# ZYNQ_SOC_JTAG.net
KiCad netlist of a schematic drawn in Altium Designer
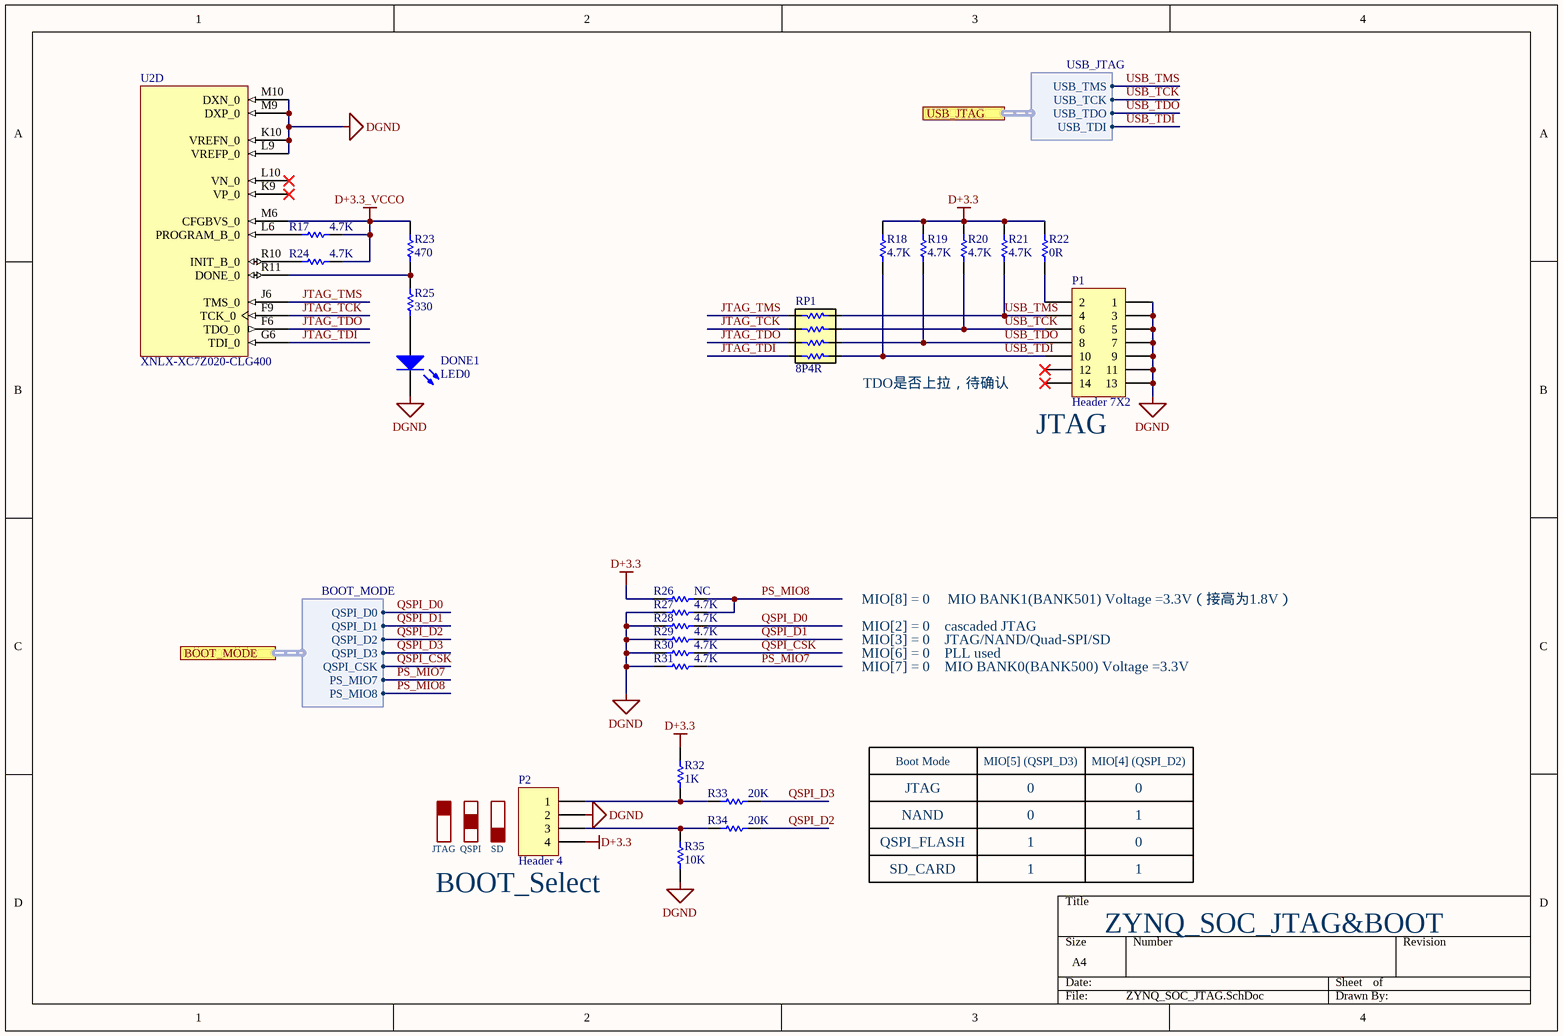
[diagram p0: ZYNQ_SOC_JTAG.SchDoc]

(export (version "E")
  (design (tool "Eeschema 10.0.6"))
  (components
    (comp (ref "DONE1")
      (value "LED0")
      (footprint "LED 0603G")
      (description "Typical INFRARED GaAs LED")
      (fields (field (name "PUBLISHER") "Altium Limited"))
      (libsource (lib "Miscellaneous Devices") (part "LED0"))
    )
    (comp (ref "P1")
      (value "Header 7X2")
      (footprint "IDC2.54-LI-2x7P")
      (description "Header, 7-Pin, Dual row")
      (fields (field (name "PUBLISHER") "Altium Limited"))
      (libsource (lib "Miscellaneous Connectors") (part "Header 7X2"))
    )
    (comp (ref "P2")
      (value "Header 4")
      (footprint "HDR1X4")
      (description "Header, 4-Pin")
      (fields (field (name "PUBLISHER") "Altium Limited"))
      (libsource (lib "Miscellaneous Connectors") (part "Header 4"))
    )
    (comp (ref "R17")
      (value "4.7K")
      (footprint "R 0402_L")
      (description "Resistor")
      (fields (field (name "PUBLISHER") "Altium Limited"))
      (libsource (lib "Miscellaneous Devices") (part "Res1"))
    )
    (comp (ref "R18")
      (value "4.7K")
      (footprint "R 0603_L")
      (description "Resistor")
      (fields (field (name "PUBLISHER") "Altium Limited"))
      (libsource (lib "Miscellaneous Devices") (part "Res1"))
    )
    (comp (ref "R19")
      (value "4.7K")
      (footprint "R 0603_L")
      (description "Resistor")
      (fields (field (name "PUBLISHER") "Altium Limited"))
      (libsource (lib "Miscellaneous Devices") (part "Res1"))
    )
    (comp (ref "R20")
      (value "4.7K")
      (footprint "R 0603_L")
      (description "Resistor")
      (fields (field (name "PUBLISHER") "Altium Limited"))
      (libsource (lib "Miscellaneous Devices") (part "Res1"))
    )
    (comp (ref "R21")
      (value "4.7K")
      (footprint "R 0603_L")
      (description "Resistor")
      (fields (field (name "PUBLISHER") "Altium Limited"))
      (libsource (lib "Miscellaneous Devices") (part "Res1"))
    )
    (comp (ref "R22")
      (value "0R")
      (footprint "R 0603_L")
      (description "Resistor")
      (fields (field (name "PUBLISHER") "Altium Limited"))
      (libsource (lib "Miscellaneous Devices") (part "Res1"))
    )
    (comp (ref "R23")
      (value "470")
      (footprint "R 0603_L")
      (description "Resistor")
      (fields (field (name "PUBLISHER") "Altium Limited"))
      (libsource (lib "Miscellaneous Devices") (part "Res1"))
    )
    (comp (ref "R24")
      (value "4.7K")
      (footprint "R 0402_L")
      (description "Resistor")
      (fields (field (name "PUBLISHER") "Altium Limited"))
      (libsource (lib "Miscellaneous Devices") (part "Res1"))
    )
    (comp (ref "R25")
      (value "330")
      (footprint "R 0603_L")
      (description "Resistor")
      (fields (field (name "PUBLISHER") "Altium Limited"))
      (libsource (lib "Miscellaneous Devices") (part "Res1"))
    )
    (comp (ref "R26")
      (value "NC")
      (footprint "R 0402_L")
      (description "Resistor")
      (fields (field (name "PUBLISHER") "Altium Limited"))
      (libsource (lib "Miscellaneous Devices") (part "Res1"))
    )
    (comp (ref "R27")
      (value "4.7K")
      (footprint "R 0402_L")
      (description "Resistor")
      (fields (field (name "PUBLISHER") "Altium Limited"))
      (libsource (lib "Miscellaneous Devices") (part "Res1"))
    )
    (comp (ref "R28")
      (value "4.7K")
      (footprint "R 0402_L")
      (description "Resistor")
      (fields (field (name "PUBLISHER") "Altium Limited"))
      (libsource (lib "Miscellaneous Devices") (part "Res1"))
    )
    (comp (ref "R29")
      (value "4.7K")
      (footprint "R 0402_L")
      (description "Resistor")
      (fields (field (name "PUBLISHER") "Altium Limited"))
      (libsource (lib "Miscellaneous Devices") (part "Res1"))
    )
    (comp (ref "R30")
      (value "4.7K")
      (footprint "R 0402_L")
      (description "Resistor")
      (fields (field (name "PUBLISHER") "Altium Limited"))
      (libsource (lib "Miscellaneous Devices") (part "Res1"))
    )
    (comp (ref "R31")
      (value "4.7K")
      (footprint "R 0402_L")
      (description "Resistor")
      (fields (field (name "PUBLISHER") "Altium Limited"))
      (libsource (lib "Miscellaneous Devices") (part "Res1"))
    )
    (comp (ref "R32")
      (value "1K")
      (footprint "R 0603_L")
      (description "Resistor")
      (fields (field (name "PUBLISHER") "Altium Limited"))
      (libsource (lib "Miscellaneous Devices") (part "Res1"))
    )
    (comp (ref "R33")
      (value "20K")
      (footprint "R 0603_L")
      (description "Resistor")
      (fields (field (name "PUBLISHER") "Altium Limited"))
      (libsource (lib "Miscellaneous Devices") (part "Res1"))
    )
    (comp (ref "R34")
      (value "20K")
      (footprint "R 0603_L")
      (description "Resistor")
      (fields (field (name "PUBLISHER") "Altium Limited"))
      (libsource (lib "Miscellaneous Devices") (part "Res1"))
    )
    (comp (ref "R35")
      (value "10K")
      (footprint "R 0603_L")
      (description "Resistor")
      (fields (field (name "PUBLISHER") "Altium Limited"))
      (libsource (lib "Miscellaneous Devices") (part "Res1"))
    )
    (comp (ref "RP1")
      (value "8P4R")
      (footprint "8P4R")
      (description "贴片排阻")
      (fields (field (name "MANUFACTURER") "NC"))
      (libsource (lib "ZYNQ7010_add") (part "8P4R"))
    )
    (comp (ref "U2")
      (value "XNLX-XC7Z020-CLG400")
      (footprint "BGA400")
      (description "xilinx双核A9处理器与FPGA集成的SoC")
      (fields (field (name "MANUFACTURER") "xilinx"))
      (libsource (lib "龙井V1") (part "XNLX-XC7Z020-CLG400"))
    )
  )
  (nets
    (net (code "3") (name "/JTAG_TCK") (class "Default")
      (node (ref "RP1") (pin "3") (pinfunction "3_3") (pintype "passive"))
      (node (ref "U2") (pin "F9") (pinfunction "TCK_0_F9") (pintype "input"))
    )
    (net (code "4") (name "/JTAG_TDI") (class "Default")
      (node (ref "RP1") (pin "1") (pinfunction "1_1") (pintype "passive"))
      (node (ref "U2") (pin "G6") (pinfunction "TDI_0_G6") (pintype "input"))
    )
    (net (code "5") (name "/JTAG_TDO") (class "Default")
      (node (ref "RP1") (pin "2") (pinfunction "2_2") (pintype "passive"))
      (node (ref "U2") (pin "F6") (pinfunction "TDO_0_F6") (pintype "output"))
    )
    (net (code "6") (name "/JTAG_TMS") (class "Default")
      (node (ref "RP1") (pin "4") (pinfunction "4_4") (pintype "passive"))
      (node (ref "U2") (pin "J6") (pinfunction "TMS_0_J6") (pintype "input"))
    )
    (net (code "7") (name "/PS_MIO7") (class "Default")
      (node (ref "R31") (pin "2") (pinfunction "2_2") (pintype "passive"))
    )
    (net (code "8") (name "/PS_MIO8") (class "Default")
      (node (ref "R26") (pin "2") (pinfunction "2_2") (pintype "passive"))
      (node (ref "R27") (pin "2") (pinfunction "2_2") (pintype "passive"))
    )
    (net (code "9") (name "/QSPI_CSK") (class "Default")
      (node (ref "R30") (pin "2") (pinfunction "2_2") (pintype "passive"))
    )
    (net (code "10") (name "/QSPI_D0") (class "Default")
      (node (ref "R28") (pin "2") (pinfunction "2_2") (pintype "passive"))
    )
    (net (code "11") (name "/QSPI_D1") (class "Default")
      (node (ref "R29") (pin "2") (pinfunction "2_2") (pintype "passive"))
    )
    (net (code "12") (name "/QSPI_D2") (class "Default")
      (node (ref "R34") (pin "2") (pinfunction "2_2") (pintype "passive"))
    )
    (net (code "13") (name "/QSPI_D3") (class "Default")
      (node (ref "R33") (pin "2") (pinfunction "2_2") (pintype "passive"))
    )
    (net (code "14") (name "/USB_TCK") (class "Default")
      (node (ref "P1") (pin "6") (pinfunction "6_6") (pintype "passive"))
      (node (ref "R20") (pin "1") (pinfunction "1_1") (pintype "passive"))
      (node (ref "RP1") (pin "7") (pinfunction "7_7") (pintype "passive"))
    )
    (net (code "15") (name "/USB_TDI") (class "Default")
      (node (ref "P1") (pin "10") (pinfunction "10_10") (pintype "passive"))
      (node (ref "R18") (pin "1") (pinfunction "1_1") (pintype "passive"))
      (node (ref "RP1") (pin "5") (pinfunction "5_5") (pintype "passive"))
    )
    (net (code "16") (name "/USB_TDO") (class "Default")
      (node (ref "P1") (pin "8") (pinfunction "8_8") (pintype "passive"))
      (node (ref "R19") (pin "1") (pinfunction "1_1") (pintype "passive"))
      (node (ref "RP1") (pin "6") (pinfunction "6_6") (pintype "passive"))
    )
    (net (code "17") (name "/USB_TMS") (class "Default")
      (node (ref "P1") (pin "4") (pinfunction "4_4") (pintype "passive"))
      (node (ref "R21") (pin "1") (pinfunction "1_1") (pintype "passive"))
      (node (ref "RP1") (pin "8") (pinfunction "8_8") (pintype "passive"))
    )
    (net (code "20") (name "D+3.3") (class "Default")
      (node (ref "P2") (pin "4") (pinfunction "4_4") (pintype "passive"))
      (node (ref "R18") (pin "2") (pinfunction "2_2") (pintype "passive"))
      (node (ref "R19") (pin "2") (pinfunction "2_2") (pintype "passive"))
      (node (ref "R20") (pin "2") (pinfunction "2_2") (pintype "passive"))
      (node (ref "R21") (pin "2") (pinfunction "2_2") (pintype "passive"))
      (node (ref "R22") (pin "2") (pinfunction "2_2") (pintype "passive"))
      (node (ref "R26") (pin "1") (pinfunction "1_1") (pintype "passive"))
      (node (ref "R32") (pin "2") (pinfunction "2_2") (pintype "passive"))
    )
    (net (code "21") (name "D+3.3_VCCO") (class "Default")
      (node (ref "R17") (pin "2") (pinfunction "2_2") (pintype "passive"))
      (node (ref "R23") (pin "2") (pinfunction "2_2") (pintype "passive"))
      (node (ref "R24") (pin "2") (pinfunction "2_2") (pintype "passive"))
      (node (ref "U2") (pin "M6") (pinfunction "CFGBVS_0_M6") (pintype "input"))
    )
    (net (code "22") (name "DGND") (class "Default")
      (node (ref "DONE1") (pin "2") (pinfunction "K_2") (pintype "passive"))
      (node (ref "P1") (pin "1") (pinfunction "1_1") (pintype "passive"))
      (node (ref "P1") (pin "11") (pinfunction "11_11") (pintype "passive"))
      (node (ref "P1") (pin "13") (pinfunction "13_13") (pintype "passive"))
      (node (ref "P1") (pin "3") (pinfunction "3_3") (pintype "passive"))
      (node (ref "P1") (pin "5") (pinfunction "5_5") (pintype "passive"))
      (node (ref "P1") (pin "7") (pinfunction "7_7") (pintype "passive"))
      (node (ref "P1") (pin "9") (pinfunction "9_9") (pintype "passive"))
      (node (ref "P2") (pin "2") (pinfunction "2_2") (pintype "passive"))
      (node (ref "R27") (pin "1") (pinfunction "1_1") (pintype "passive"))
      (node (ref "R28") (pin "1") (pinfunction "1_1") (pintype "passive"))
      (node (ref "R29") (pin "1") (pinfunction "1_1") (pintype "passive"))
      (node (ref "R30") (pin "1") (pinfunction "1_1") (pintype "passive"))
      (node (ref "R31") (pin "1") (pinfunction "1_1") (pintype "passive"))
      (node (ref "R35") (pin "1") (pinfunction "1_1") (pintype "passive"))
      (node (ref "U2") (pin "K10") (pinfunction "VREFN_0_K10") (pintype "input"))
      (node (ref "U2") (pin "L9") (pinfunction "VREFP_0_L9") (pintype "input"))
      (node (ref "U2") (pin "M10") (pinfunction "DXN_0_M10") (pintype "input"))
      (node (ref "U2") (pin "M9") (pinfunction "DXP_0_M9") (pintype "input"))
    )
    (net (code "23") (name "Net-(DONE1-A)") (class "Default")
      (node (ref "DONE1") (pin "1") (pinfunction "A_1") (pintype "passive"))
      (node (ref "R25") (pin "1") (pinfunction "1_1") (pintype "passive"))
    )
    (net (code "24") (name "Net-(P1-Pad2)") (class "Default")
      (node (ref "P1") (pin "2") (pinfunction "2_2") (pintype "passive"))
      (node (ref "R22") (pin "1") (pinfunction "1_1") (pintype "passive"))
    )
    (net (code "25") (name "Net-(P2-Pad1)") (class "Default")
      (node (ref "P2") (pin "1") (pinfunction "1_1") (pintype "passive"))
      (node (ref "R32") (pin "1") (pinfunction "1_1") (pintype "passive"))
      (node (ref "R33") (pin "1") (pinfunction "1_1") (pintype "passive"))
    )
    (net (code "26") (name "Net-(P2-Pad3)") (class "Default")
      (node (ref "P2") (pin "3") (pinfunction "3_3") (pintype "passive"))
      (node (ref "R34") (pin "1") (pinfunction "1_1") (pintype "passive"))
      (node (ref "R35") (pin "2") (pinfunction "2_2") (pintype "passive"))
    )
    (net (code "27") (name "Net-(U2D-DONE_0)") (class "Default")
      (node (ref "R23") (pin "1") (pinfunction "1_1") (pintype "passive"))
      (node (ref "R25") (pin "2") (pinfunction "2_2") (pintype "passive"))
      (node (ref "U2") (pin "R11") (pinfunction "DONE_0_R11") (pintype "bidirectional"))
    )
    (net (code "28") (name "Net-(U2D-INIT_B_0)") (class "Default")
      (node (ref "R24") (pin "1") (pinfunction "1_1") (pintype "passive"))
      (node (ref "U2") (pin "R10") (pinfunction "INIT_B_0_R10") (pintype "bidirectional"))
    )
    (net (code "29") (name "Net-(U2D-PROGRAM_B_0)") (class "Default")
      (node (ref "R17") (pin "1") (pinfunction "1_1") (pintype "passive"))
      (node (ref "U2") (pin "L6") (pinfunction "PROGRAM_B_0_L6") (pintype "input"))
    )
    (net (code "30") (name "unconnected-(P1-Pad12)") (class "Default")
      (node (ref "P1") (pin "12") (pinfunction "12_12") (pintype "passive+no_connect"))
    )
    (net (code "31") (name "unconnected-(P1-Pad14)") (class "Default")
      (node (ref "P1") (pin "14") (pinfunction "14_14") (pintype "passive+no_connect"))
    )
    (net (code "32") (name "unconnected-(U2D-VN_0-PadL10)") (class "Default")
      (node (ref "U2") (pin "L10") (pinfunction "VN_0_L10") (pintype "input+no_connect"))
    )
    (net (code "33") (name "unconnected-(U2D-VP_0-PadK9)") (class "Default")
      (node (ref "U2") (pin "K9") (pinfunction "VP_0_K9") (pintype "input+no_connect"))
    )
  )
)
